# Dimmer2_RevA.net
KiCad netlist of a schematic drawn in EAGLE
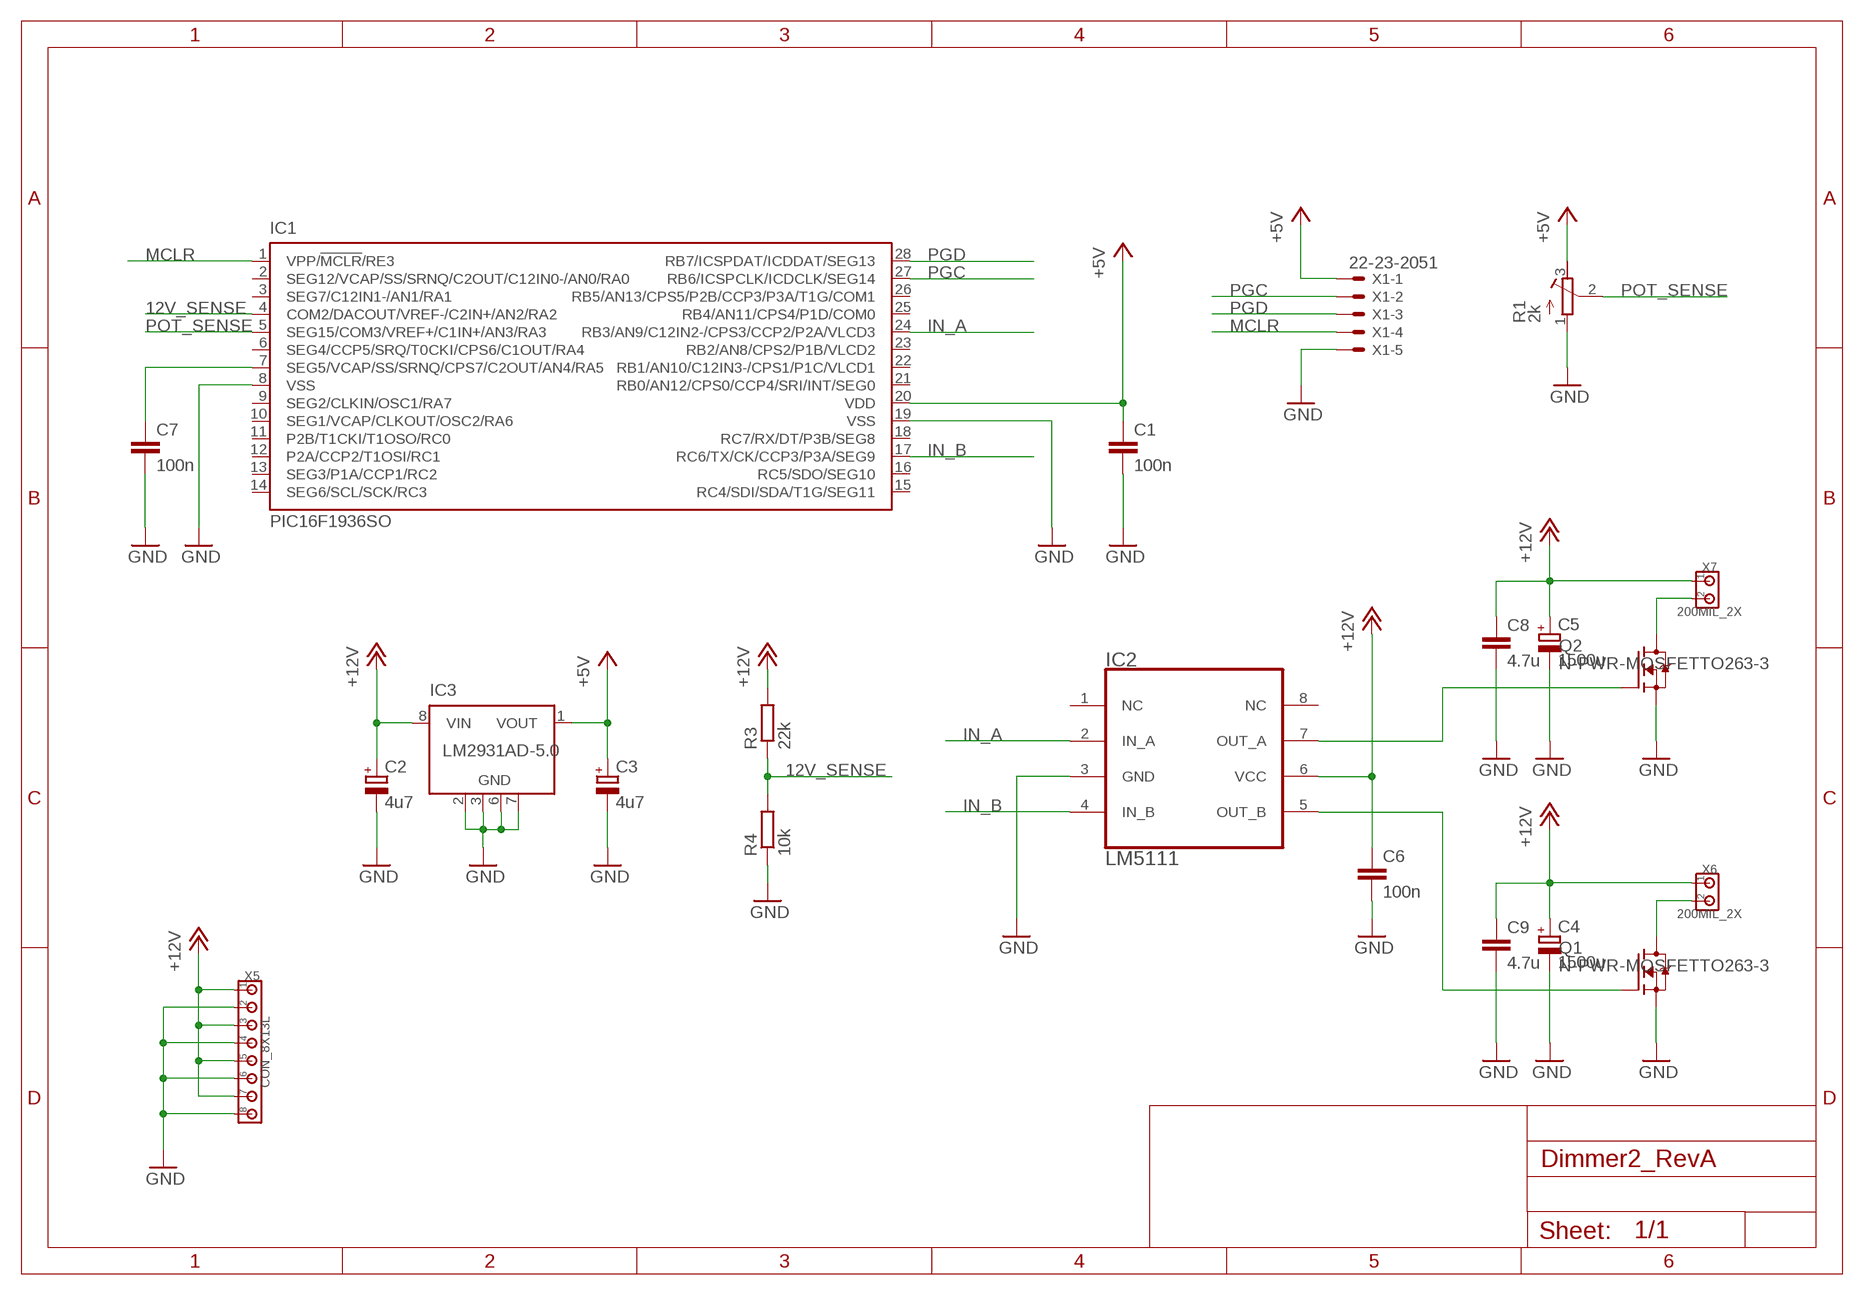
[diagram p0: schematic, sheet 1]

(export (version "E")
  (design (tool "Eeschema 10.0.6"))
  (components
    (comp (ref "C1")
      (value "100n")
      (footprint "eagle-import:C0805")
      (libsource (lib "eagle-import") (part "CC0805"))
    )
    (comp (ref "C2")
      (value "4u7")
      (footprint "eagle-import:SMC_C")
      (libsource (lib "eagle-import") (part "C_POLARIZEDSMC_C"))
    )
    (comp (ref "C3")
      (value "4u7")
      (footprint "eagle-import:SMC_C")
      (libsource (lib "eagle-import") (part "C_POLARIZEDSMC_C"))
    )
    (comp (ref "C4")
      (value "1500u")
      (footprint "eagle-import:10MM")
      (libsource (lib "eagle-import") (part "C_POLARIZED10MM"))
    )
    (comp (ref "C5")
      (value "1500u")
      (footprint "eagle-import:10MM")
      (libsource (lib "eagle-import") (part "C_POLARIZED10MM"))
    )
    (comp (ref "C6")
      (value "100n")
      (footprint "eagle-import:C0805")
      (libsource (lib "eagle-import") (part "CC0805"))
    )
    (comp (ref "C7")
      (value "100n")
      (footprint "eagle-import:C0805")
      (libsource (lib "eagle-import") (part "CC0805"))
    )
    (comp (ref "C8")
      (value "4.7u")
      (footprint "eagle-import:C1206")
      (libsource (lib "eagle-import") (part "CC1206"))
    )
    (comp (ref "C9")
      (value "4.7u")
      (footprint "eagle-import:C1206")
      (libsource (lib "eagle-import") (part "CC1206"))
    )
    (comp (ref "IC1")
      (value "PIC16F1936SO")
      (footprint "eagle-import:SO28W")
      (libsource (lib "eagle-import") (part "PIC16F19SO36"))
    )
    (comp (ref "IC2")
      (value "LM5111")
      (footprint "eagle-import:SOIC8")
      (libsource (lib "eagle-import") (part "LM5111"))
    )
    (comp (ref "IC3")
      (value "LM2931AD-5.0")
      (footprint "eagle-import:SO8")
      (libsource (lib "eagle-import") (part "LM2931AD-5.0"))
    )
    (comp (ref "Q1")
      (value "N-PWR-MOSFETTO263-3")
      (footprint "eagle-import:TO263-3")
      (libsource (lib "eagle-import") (part "N-PWR-MOSFETTO263-3"))
    )
    (comp (ref "Q2")
      (value "N-PWR-MOSFETTO263-3")
      (footprint "eagle-import:TO263-3")
      (libsource (lib "eagle-import") (part "N-PWR-MOSFETTO263-3"))
    )
    (comp (ref "R1")
      (value "2k")
      (footprint "eagle-import:CONTELEC")
      (libsource (lib "eagle-import") (part "TRIMMER"))
    )
    (comp (ref "R3")
      (value "22k")
      (footprint "eagle-import:R0805")
      (libsource (lib "eagle-import") (part "RESISTORR0805"))
    )
    (comp (ref "R4")
      (value "10k")
      (footprint "eagle-import:R0805")
      (libsource (lib "eagle-import") (part "RESISTORR0805"))
    )
    (comp (ref "X1")
      (value "22-23-2051")
      (footprint "eagle-import:22-23-2051")
      (fields (field (name "MF") "MOLEX"))
      (libsource (lib "eagle-import") (part "22-23-2051"))
    )
    (comp (ref "X5")
      (value "CON_8X13L")
      (footprint "eagle-import:200MIL_8X")
      (libsource (lib "eagle-import") (part "CON_8X13L"))
    )
    (comp (ref "X6")
      (value "200MIL_2X")
      (footprint "eagle-import:200MIL_2X")
      (libsource (lib "eagle-import") (part "200MIL_2X"))
    )
    (comp (ref "X7")
      (value "200MIL_2X")
      (footprint "eagle-import:200MIL_2X")
      (libsource (lib "eagle-import") (part "200MIL_2X"))
    )
  )
  (nets
    (net (code "1") (name "+5V") (class "Default")
      (node (ref "C1") (pin "1") (pinfunction "1_1") (pintype "passive"))
      (node (ref "C3") (pin "+") (pinfunction "+_+") (pintype "passive"))
      (node (ref "IC1") (pin "20") (pinfunction "VDD_20") (pintype "power_in"))
      (node (ref "IC3") (pin "1") (pinfunction "VOUT_1") (pintype "output"))
      (node (ref "R1") (pin "3") (pinfunction "CW_3") (pintype "passive"))
      (node (ref "X1") (pin "1") (pinfunction "S_1") (pintype "passive"))
    )
    (net (code "2") (name "+12V") (class "Default")
      (node (ref "C2") (pin "+") (pinfunction "+_+") (pintype "passive"))
      (node (ref "C4") (pin "+") (pinfunction "+_+") (pintype "passive"))
      (node (ref "C5") (pin "+") (pinfunction "+_+") (pintype "passive"))
      (node (ref "C6") (pin "1") (pinfunction "1_1") (pintype "passive"))
      (node (ref "C8") (pin "1") (pinfunction "1_1") (pintype "passive"))
      (node (ref "C9") (pin "1") (pinfunction "1_1") (pintype "passive"))
      (node (ref "IC2") (pin "6") (pinfunction "VCC_6") (pintype "input"))
      (node (ref "IC3") (pin "8") (pinfunction "VIN_8") (pintype "passive"))
      (node (ref "R3") (pin "2") (pinfunction "2_2") (pintype "passive"))
      (node (ref "X5") (pin "1") (pinfunction "P$1_1") (pintype "passive"))
      (node (ref "X5") (pin "3") (pinfunction "P$3_3") (pintype "passive"))
      (node (ref "X5") (pin "5") (pinfunction "P$5_5") (pintype "passive"))
      (node (ref "X5") (pin "7") (pinfunction "P$7_7") (pintype "passive"))
      (node (ref "X6") (pin "1") (pinfunction "1_1") (pintype "passive"))
      (node (ref "X7") (pin "1") (pinfunction "1_1") (pintype "passive"))
    )
    (net (code "3") (name "/12V_SENSE") (class "Default")
      (node (ref "IC1") (pin "4") (pinfunction "COM2/DACOUT/VREF-/C2IN+/AN2/RA2_4") (pintype "bidirectional"))
      (node (ref "R3") (pin "1") (pinfunction "1_1") (pintype "passive"))
      (node (ref "R4") (pin "2") (pinfunction "2_2") (pintype "passive"))
    )
    (net (code "4") (name "/IN_A") (class "Default")
      (node (ref "IC1") (pin "24") (pinfunction "RB3/AN9/C12IN2-/CPS3/CCP2/P2A/VLCD3_24") (pintype "bidirectional"))
      (node (ref "IC2") (pin "2") (pinfunction "IN_A_2") (pintype "input"))
    )
    (net (code "5") (name "/IN_B") (class "Default")
      (node (ref "IC1") (pin "17") (pinfunction "RC6/TX/CK/CCP3/P3A/SEG9_17") (pintype "bidirectional"))
      (node (ref "IC2") (pin "4") (pinfunction "IN_B_4") (pintype "passive"))
    )
    (net (code "6") (name "/MCLR") (class "Default")
      (node (ref "IC1") (pin "1") (pinfunction "VPP/~{MCLR}/RE3_1") (pintype "input"))
      (node (ref "X1") (pin "4") (pinfunction "S_4") (pintype "passive"))
    )
    (net (code "7") (name "/NC") (class "Default")
      (node (ref "IC2") (pin "8") (pinfunction "NC_8") (pintype "power_in"))
    )
    (net (code "8") (name "/PGC") (class "Default")
      (node (ref "IC1") (pin "27") (pinfunction "RB6/ICSPCLK/ICDCLK/SEG14_27") (pintype "bidirectional"))
      (node (ref "X1") (pin "2") (pinfunction "S_2") (pintype "passive"))
    )
    (net (code "9") (name "/PGD") (class "Default")
      (node (ref "IC1") (pin "28") (pinfunction "RB7/ICSPDAT/ICDDAT/SEG13_28") (pintype "bidirectional"))
      (node (ref "X1") (pin "3") (pinfunction "S_3") (pintype "passive"))
    )
    (net (code "10") (name "/POT_SENSE") (class "Default")
      (node (ref "IC1") (pin "5") (pinfunction "SEG15/COM3/VREF+/C1IN+/AN3/RA3_5") (pintype "bidirectional"))
      (node (ref "R1") (pin "2") (pinfunction "WIPER_2") (pintype "passive"))
    )
    (net (code "11") (name "GND") (class "Default")
      (node (ref "C1") (pin "2") (pinfunction "2_2") (pintype "passive"))
      (node (ref "C2") (pin "-") (pinfunction "-_-") (pintype "passive"))
      (node (ref "C3") (pin "-") (pinfunction "-_-") (pintype "passive"))
      (node (ref "C4") (pin "-") (pinfunction "-_-") (pintype "passive"))
      (node (ref "C5") (pin "-") (pinfunction "-_-") (pintype "passive"))
      (node (ref "C6") (pin "2") (pinfunction "2_2") (pintype "passive"))
      (node (ref "C7") (pin "2") (pinfunction "2_2") (pintype "passive"))
      (node (ref "C8") (pin "2") (pinfunction "2_2") (pintype "passive"))
      (node (ref "C9") (pin "2") (pinfunction "2_2") (pintype "passive"))
      (node (ref "IC1") (pin "19") (pinfunction "VSS_19") (pintype "power_in"))
      (node (ref "IC1") (pin "8") (pinfunction "VSS_8") (pintype "power_in"))
      (node (ref "IC2") (pin "3") (pinfunction "GND_3") (pintype "input"))
      (node (ref "IC3") (pin "2") (pinfunction "GND_2") (pintype "power_in"))
      (node (ref "IC3") (pin "3") (pinfunction "GND_3") (pintype "power_in"))
      (node (ref "IC3") (pin "6") (pinfunction "GND_6") (pintype "power_in"))
      (node (ref "IC3") (pin "7") (pinfunction "GND_7") (pintype "power_in"))
      (node (ref "Q1") (pin "3") (pinfunction "S_3") (pintype "passive"))
      (node (ref "Q2") (pin "3") (pinfunction "S_3") (pintype "passive"))
      (node (ref "R1") (pin "1") (pinfunction "CCW_1") (pintype "passive"))
      (node (ref "R4") (pin "1") (pinfunction "1_1") (pintype "passive"))
      (node (ref "X1") (pin "5") (pinfunction "S_5") (pintype "passive"))
      (node (ref "X5") (pin "2") (pinfunction "P$2_2") (pintype "passive"))
      (node (ref "X5") (pin "4") (pinfunction "P$4_4") (pintype "passive"))
      (node (ref "X5") (pin "6") (pinfunction "P$6_6") (pintype "passive"))
      (node (ref "X5") (pin "8") (pinfunction "P$8_8") (pintype "passive"))
    )
    (net (code "12") (name "Net-(IC1-SEG5{slash}VCAP{slash}SS{slash}SRNQ{slash}CPS7{slash}C2OUT{slash}AN4{slash}RA5)") (class "Default")
      (node (ref "C7") (pin "1") (pinfunction "1_1") (pintype "passive"))
      (node (ref "IC1") (pin "7") (pinfunction "SEG5/VCAP/SS/SRNQ/CPS7/C2OUT/AN4/RA5_7") (pintype "bidirectional"))
    )
    (net (code "13") (name "Net-(IC2-OUT_A)") (class "Default")
      (node (ref "IC2") (pin "7") (pinfunction "OUT_A_7") (pintype "input"))
      (node (ref "Q2") (pin "1") (pinfunction "G_1") (pintype "passive"))
    )
    (net (code "14") (name "Net-(IC2-OUT_B)") (class "Default")
      (node (ref "IC2") (pin "5") (pinfunction "OUT_B_5") (pintype "bidirectional"))
      (node (ref "Q1") (pin "1") (pinfunction "G_1") (pintype "passive"))
    )
    (net (code "15") (name "Net-(Q1-D)") (class "Default")
      (node (ref "Q1") (pin "TAB") (pinfunction "D_TAB") (pintype "passive"))
      (node (ref "X6") (pin "2") (pinfunction "2_2") (pintype "passive"))
    )
    (net (code "16") (name "Net-(Q2-D)") (class "Default")
      (node (ref "Q2") (pin "TAB") (pinfunction "D_TAB") (pintype "passive"))
      (node (ref "X7") (pin "2") (pinfunction "2_2") (pintype "passive"))
    )
    (net (code "17") (name "unconnected-(IC1-P2A{slash}CCP2{slash}T1OSI{slash}RC1-Pad12)") (class "Default")
      (node (ref "IC1") (pin "12") (pinfunction "P2A/CCP2/T1OSI/RC1_12") (pintype "bidirectional"))
    )
    (net (code "18") (name "unconnected-(IC1-P2B{slash}T1CKI{slash}T1OSO{slash}RC0-Pad11)") (class "Default")
      (node (ref "IC1") (pin "11") (pinfunction "P2B/T1CKI/T1OSO/RC0_11") (pintype "bidirectional"))
    )
    (net (code "19") (name "unconnected-(IC1-RB0{slash}AN12{slash}CPS0{slash}CCP4{slash}SRI{slash}INT{slash}SEG0-Pad21)") (class "Default")
      (node (ref "IC1") (pin "21") (pinfunction "RB0/AN12/CPS0/CCP4/SRI/INT/SEG0_21") (pintype "bidirectional"))
    )
    (net (code "20") (name "unconnected-(IC1-RB1{slash}AN10{slash}C12IN3-{slash}CPS1{slash}P1C{slash}VLCD1-Pad22)") (class "Default")
      (node (ref "IC1") (pin "22") (pinfunction "RB1/AN10/C12IN3-/CPS1/P1C/VLCD1_22") (pintype "bidirectional"))
    )
    (net (code "21") (name "unconnected-(IC1-RB2{slash}AN8{slash}CPS2{slash}P1B{slash}VLCD2-Pad23)") (class "Default")
      (node (ref "IC1") (pin "23") (pinfunction "RB2/AN8/CPS2/P1B/VLCD2_23") (pintype "bidirectional"))
    )
    (net (code "22") (name "unconnected-(IC1-RB4{slash}AN11{slash}CPS4{slash}P1D{slash}COM0-Pad25)") (class "Default")
      (node (ref "IC1") (pin "25") (pinfunction "RB4/AN11/CPS4/P1D/COM0_25") (pintype "bidirectional"))
    )
    (net (code "23") (name "unconnected-(IC1-RB5{slash}AN13{slash}CPS5{slash}P2B{slash}CCP3{slash}P3A{slash}T1G{slash}COM1-Pad26)") (class "Default")
      (node (ref "IC1") (pin "26") (pinfunction "RB5/AN13/CPS5/P2B/CCP3/P3A/T1G/COM1_26") (pintype "bidirectional"))
    )
    (net (code "24") (name "unconnected-(IC1-RC4{slash}SDI{slash}SDA{slash}T1G{slash}SEG11-Pad15)") (class "Default")
      (node (ref "IC1") (pin "15") (pinfunction "RC4/SDI/SDA/T1G/SEG11_15") (pintype "bidirectional"))
    )
    (net (code "25") (name "unconnected-(IC1-RC5{slash}SDO{slash}SEG10-Pad16)") (class "Default")
      (node (ref "IC1") (pin "16") (pinfunction "RC5/SDO/SEG10_16") (pintype "bidirectional"))
    )
    (net (code "26") (name "unconnected-(IC1-RC7{slash}RX{slash}DT{slash}P3B{slash}SEG8-Pad18)") (class "Default")
      (node (ref "IC1") (pin "18") (pinfunction "RC7/RX/DT/P3B/SEG8_18") (pintype "bidirectional"))
    )
    (net (code "27") (name "unconnected-(IC1-SEG1{slash}VCAP{slash}CLKOUT{slash}OSC2{slash}RA6-Pad10)") (class "Default")
      (node (ref "IC1") (pin "10") (pinfunction "SEG1/VCAP/CLKOUT/OSC2/RA6_10") (pintype "bidirectional"))
    )
    (net (code "28") (name "unconnected-(IC1-SEG2{slash}CLKIN{slash}OSC1{slash}RA7-Pad9)") (class "Default")
      (node (ref "IC1") (pin "9") (pinfunction "SEG2/CLKIN/OSC1/RA7_9") (pintype "bidirectional"))
    )
    (net (code "29") (name "unconnected-(IC1-SEG3{slash}P1A{slash}CCP1{slash}RC2-Pad13)") (class "Default")
      (node (ref "IC1") (pin "13") (pinfunction "SEG3/P1A/CCP1/RC2_13") (pintype "bidirectional"))
    )
    (net (code "30") (name "unconnected-(IC1-SEG4{slash}CCP5{slash}SRQ{slash}T0CKI{slash}CPS6{slash}C1OUT{slash}RA4-Pad6)") (class "Default")
      (node (ref "IC1") (pin "6") (pinfunction "SEG4/CCP5/SRQ/T0CKI/CPS6/C1OUT/RA4_6") (pintype "bidirectional"))
    )
    (net (code "31") (name "unconnected-(IC1-SEG6{slash}SCL{slash}SCK{slash}RC3-Pad14)") (class "Default")
      (node (ref "IC1") (pin "14") (pinfunction "SEG6/SCL/SCK/RC3_14") (pintype "bidirectional"))
    )
    (net (code "32") (name "unconnected-(IC1-SEG7{slash}C12IN1-{slash}AN1{slash}RA1-Pad3)") (class "Default")
      (node (ref "IC1") (pin "3") (pinfunction "SEG7/C12IN1-/AN1/RA1_3") (pintype "bidirectional"))
    )
    (net (code "33") (name "unconnected-(IC1-SEG12{slash}VCAP{slash}SS{slash}SRNQ{slash}C2OUT{slash}C12IN0-{slash}AN0{slash}RA0-Pad2)") (class "Default")
      (node (ref "IC1") (pin "2") (pinfunction "SEG12/VCAP/SS/SRNQ/C2OUT/C12IN0-/AN0/RA0_2") (pintype "bidirectional"))
    )
    (net (code "34") (name "unconnected-(IC2-NC-Pad1)") (class "Default")
      (node (ref "IC2") (pin "1") (pinfunction "NC_1") (pintype "input"))
    )
  )
)
